# Arduino-Headers.net
KiCad netlist of a schematic drawn in Altium Designer
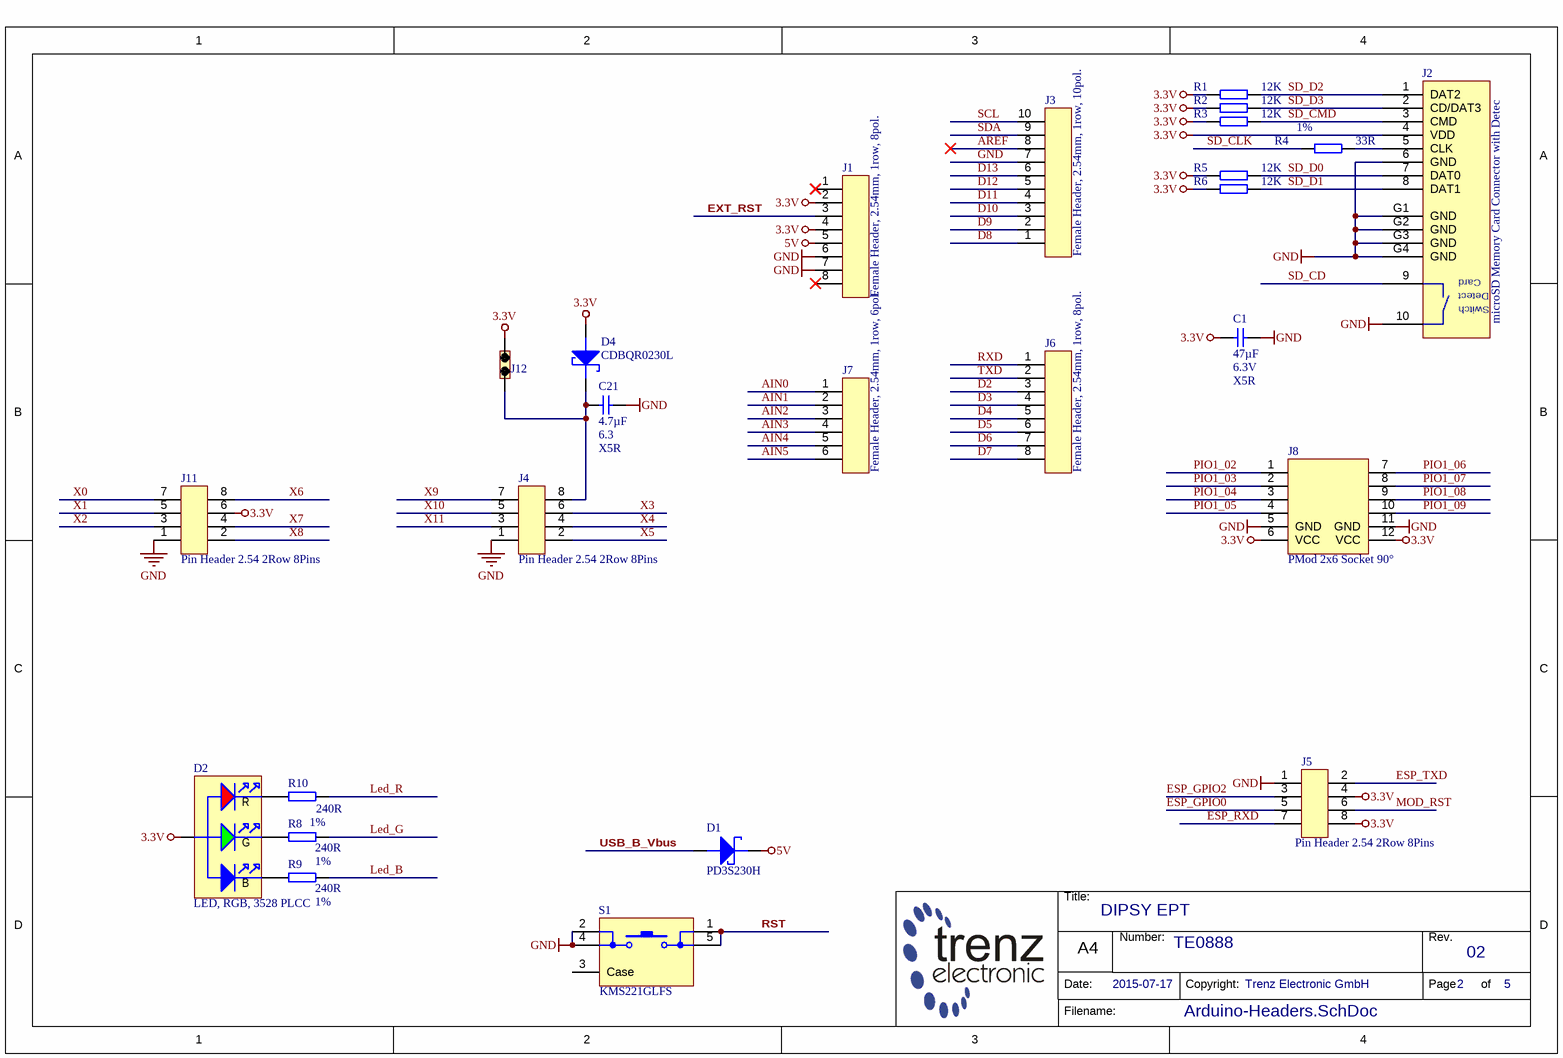
[diagram p0: Arduino-Headers.SchDoc]

(export (version "E")
  (design (tool "Eeschema 10.0.6"))
  (components
    (comp (ref "C1")
      (value "47µF")
      (footprint "CAPC2012X135N")
      (description "KON 47µF 6,3V  X5R SMD 20%")
      (fields
        (field (name "VOLTAGE") "6.3V")
        (field (name "TECHNOLOGY") "X5R")
        (field (name "TOLERANCE") "20%")
      )
      (libsource (lib "TE") (part "CAP-NP"))
    )
    (comp (ref "C21")
      (value "4.7µF")
      (footprint "CAPC1005X60N")
      (description "KON 4.7µF 6.3V X5R SMD 20%")
      (fields
        (field (name "VOLTAGE") "6.3")
        (field (name "TECHNOLOGY") "X5R")
        (field (name "TOLERANCE") "20%")
      )
      (libsource (lib "TE") (part "CAP-NP"))
    )
    (comp (ref "D1") (value "PD3S230H") (footprint "PowerDI323") (libsource (lib "TE") (part "SCHOTTKY")))
    (comp (ref "D2")
      (value "LED, RGB, 3528 PLCC")
      (footprint "PLCC150P360X280X190-4N-WE")
      (libsource (lib "TE") (part "150141M173100"))
    )
    (comp (ref "D4")
      (value "CDBQR0230L")
      (footprint "DIOC1006X55N")
      (fields (field (name "VOLTAGE") "0.2A"))
      (libsource (lib "TE") (part "SCHOTTKY"))
    )
    (comp (ref "J1")
      (value "Female Header, 2.54mm, 1row, 8pol.")
      (footprint "BUCHSENLEISTE-2.54-8-1R")
      (description "Buchsenleiste 1 reihig präz. 8 pol.")
      (libsource (lib "TE") (part "CON-8"))
    )
    (comp (ref "J2")
      (value "microSD Memory Card Connector with Detec")
      (footprint "104031-0811")
      (description "microSD Memory Card Connector with Detect Switch")
      (libsource (lib "TE") (part "104031-0811"))
    )
    (comp (ref "J3")
      (value "Female Header, 2.54mm, 1row, 10pol.")
      (footprint "BUCHSENLEISTE-2.54-10-1R")
      (description "Buchsenleiste 1 reihig präz. 10 pol.")
      (libsource (lib "TE") (part "CON-10"))
    )
    (comp (ref "J4")
      (value "Pin Header 2.54 2Row 8Pins")
      (footprint "STIFTLEISTE2_54 OG 2R-8")
      (description "Stiftleiste gerade 2-reihig, 8pol.")
      (libsource (lib "") (part "CON-8_2"))
    )
    (comp (ref "J5")
      (value "Pin Header 2.54 2Row 8Pins")
      (footprint "STIFTLEISTE2_54 OG 2R-8")
      (description "Stiftleiste gerade 2-reihig, 8pol.")
      (libsource (lib "") (part "CON-8_1"))
    )
    (comp (ref "J6")
      (value "Female Header, 2.54mm, 1row, 8pol.")
      (footprint "BUCHSENLEISTE-2.54-8-1R")
      (description "Buchsenleiste 1 reihig präz. 8 pol.")
      (libsource (lib "TE") (part "CON-8"))
    )
    (comp (ref "J7")
      (value "Female Header, 2.54mm, 1row, 6pol.")
      (footprint "BUCHSENLEISTE-2.54-6-1R")
      (description "Buchsenleiste 1 reihig präz. 6 pol.")
      (libsource (lib "TE") (part "CON-6"))
    )
    (comp (ref "J8")
      (value "PMod 2x6 Socket 90°")
      (footprint "PMod2x6")
      (libsource (lib "TE") (part "PMod2x6"))
    )
    (comp (ref "J11")
      (value "Pin Header 2.54 2Row 8Pins")
      (footprint "STIFTLEISTE2_54 OG 2R-8")
      (description "Stiftleiste gerade 2-reihig, 8pol.")
      (libsource (lib "") (part "CON-8_2"))
    )
    (comp (ref "J12")
      (value "JUMPER2.54-2")
      (footprint "JUMPER2_54-2")
      (description "Stiftleiste gerade 1-reihig, 2pol.")
      (libsource (lib "TE") (part "JUMPER2.54-2"))
    )
    (comp (ref "R1")
      (value "12K")
      (footprint "RESC1005X40N")
      (description "WID SMD 12K 1% 0,063W")
      (libsource (lib "TE") (part "RES"))
    )
    (comp (ref "R2")
      (value "12K")
      (footprint "RESC1005X40N")
      (description "WID SMD 12K 1% 0,063W")
      (libsource (lib "TE") (part "RES"))
    )
    (comp (ref "R3")
      (value "12K")
      (footprint "RESC1005X40N")
      (description "WID SMD 12K 1% 0,063W")
      (libsource (lib "TE") (part "RES"))
    )
    (comp (ref "R4")
      (value "33R")
      (footprint "RESC0603X26N")
      (description "WID SMD 33R 1% 0,05W")
      (fields (field (name "TOLERANCE") "1%"))
      (libsource (lib "TE") (part "RES"))
    )
    (comp (ref "R5")
      (value "12K")
      (footprint "RESC1005X40N")
      (description "WID SMD 12K 1% 0,063W")
      (libsource (lib "TE") (part "RES"))
    )
    (comp (ref "R6")
      (value "12K")
      (footprint "RESC1005X40N")
      (description "WID SMD 12K 1% 0,063W")
      (libsource (lib "TE") (part "RES"))
    )
    (comp (ref "R8")
      (value "240R")
      (footprint "RESC1005X40N")
      (description "WID SMD 240R 1% 0,063W")
      (fields (field (name "TOLERANCE") "1%"))
      (libsource (lib "TE") (part "RES"))
    )
    (comp (ref "R9")
      (value "240R")
      (footprint "RESC1005X40N")
      (description "WID SMD 240R 1% 0,063W")
      (fields (field (name "TOLERANCE") "1%"))
      (libsource (lib "TE") (part "RES"))
    )
    (comp (ref "R10")
      (value "240R")
      (footprint "RESC1005X40N")
      (description "WID SMD 240R 1% 0,063W")
      (fields (field (name "TOLERANCE") "1%"))
      (libsource (lib "TE") (part "RES"))
    )
    (comp (ref "S1")
      (value "KMS221GLFS")
      (footprint "KMS2xxGLFS")
      (description "KMS221GLFS - SWITCH, SPST, 0.05A, 32VDC, SMD")
      (libsource (lib "TE") (part "KMS2xxGLFS"))
    )
  )
  (nets
    (net (code "1") (name "/AIN0") (class "Default") (node (ref "J7") (pin "1") (pintype "passive")))
    (net (code "2") (name "/AIN1") (class "Default") (node (ref "J7") (pin "2") (pintype "passive")))
    (net (code "3") (name "/AIN2") (class "Default") (node (ref "J7") (pin "3") (pintype "passive")))
    (net (code "4") (name "/AIN3") (class "Default") (node (ref "J7") (pin "4") (pintype "passive")))
    (net (code "5") (name "/AIN4") (class "Default") (node (ref "J7") (pin "5") (pintype "passive")))
    (net (code "6") (name "/AIN5") (class "Default") (node (ref "J7") (pin "6") (pintype "passive")))
    (net (code "7") (name "/AREF") (class "Default")
      (node (ref "J3") (pin "8") (pinfunction "8_8") (pintype "passive+no_connect"))
    )
    (net (code "8") (name "/D2") (class "Default") (node (ref "J6") (pin "3") (pintype "passive")))
    (net (code "9") (name "/D3") (class "Default") (node (ref "J6") (pin "4") (pintype "passive")))
    (net (code "10") (name "/D4") (class "Default") (node (ref "J6") (pin "5") (pintype "passive")))
    (net (code "11") (name "/D5") (class "Default") (node (ref "J6") (pin "6") (pintype "passive")))
    (net (code "12") (name "/D6") (class "Default") (node (ref "J6") (pin "7") (pintype "passive")))
    (net (code "13") (name "/D7") (class "Default") (node (ref "J6") (pin "8") (pintype "passive")))
    (net (code "14") (name "/D8") (class "Default")
      (node (ref "J3") (pin "1") (pinfunction "1_1") (pintype "passive"))
    )
    (net (code "15") (name "/D9") (class "Default")
      (node (ref "J3") (pin "2") (pinfunction "2_2") (pintype "passive"))
    )
    (net (code "16") (name "/D10") (class "Default")
      (node (ref "J3") (pin "3") (pinfunction "3_3") (pintype "passive"))
    )
    (net (code "17") (name "/D11") (class "Default")
      (node (ref "J3") (pin "4") (pinfunction "4_4") (pintype "passive"))
    )
    (net (code "18") (name "/D12") (class "Default")
      (node (ref "J3") (pin "5") (pinfunction "5_5") (pintype "passive"))
    )
    (net (code "19") (name "/D13") (class "Default")
      (node (ref "J3") (pin "6") (pinfunction "6_6") (pintype "passive"))
    )
    (net (code "20") (name "/ESP_GPIO0") (class "Default") (node (ref "J5") (pin "5") (pintype "passive")))
    (net (code "21") (name "/ESP_GPIO2") (class "Default") (node (ref "J5") (pin "3") (pintype "passive")))
    (net (code "22") (name "/ESP_RXD") (class "Default") (node (ref "J5") (pin "7") (pintype "passive")))
    (net (code "23") (name "/ESP_TXD") (class "Default") (node (ref "J5") (pin "2") (pintype "passive")))
    (net (code "24") (name "/EXT_RST") (class "Default") (node (ref "J1") (pin "3") (pintype "passive")))
    (net (code "25") (name "/Led_B") (class "Default")
      (node (ref "R9") (pin "1") (pinfunction "1_1") (pintype "passive"))
    )
    (net (code "26") (name "/Led_G") (class "Default")
      (node (ref "R8") (pin "1") (pinfunction "1_1") (pintype "passive"))
    )
    (net (code "27") (name "/Led_R") (class "Default")
      (node (ref "R10") (pin "1") (pinfunction "1_1") (pintype "passive"))
    )
    (net (code "28") (name "/MOD_RST") (class "Default") (node (ref "J5") (pin "6") (pintype "passive")))
    (net (code "29") (name "/PIO1_02") (class "Default") (node (ref "J8") (pin "1") (pintype "passive")))
    (net (code "30") (name "/PIO1_03") (class "Default") (node (ref "J8") (pin "2") (pintype "passive")))
    (net (code "31") (name "/PIO1_04") (class "Default") (node (ref "J8") (pin "3") (pintype "passive")))
    (net (code "32") (name "/PIO1_05") (class "Default") (node (ref "J8") (pin "4") (pintype "passive")))
    (net (code "33") (name "/PIO1_06") (class "Default") (node (ref "J8") (pin "7") (pintype "passive")))
    (net (code "34") (name "/PIO1_07") (class "Default") (node (ref "J8") (pin "8") (pintype "passive")))
    (net (code "35") (name "/PIO1_08") (class "Default") (node (ref "J8") (pin "9") (pintype "passive")))
    (net (code "36") (name "/PIO1_09") (class "Default") (node (ref "J8") (pin "10") (pintype "passive")))
    (net (code "37") (name "/RST") (class "Default")
      (node (ref "S1") (pin "1") (pinfunction "1_1") (pintype "passive"))
      (node (ref "S1") (pin "5") (pinfunction "5_5") (pintype "passive"))
    )
    (net (code "38") (name "/RXD") (class "Default") (node (ref "J6") (pin "1") (pintype "passive")))
    (net (code "39") (name "/SCL") (class "Default")
      (node (ref "J3") (pin "10") (pinfunction "10_10") (pintype "passive"))
    )
    (net (code "40") (name "/SDA") (class "Default")
      (node (ref "J3") (pin "9") (pinfunction "9_9") (pintype "passive"))
    )
    (net (code "41") (name "/SD_CD") (class "Default")
      (node (ref "J2") (pin "9") (pinfunction "CDSW_9") (pintype "passive"))
    )
    (net (code "42") (name "/SD_CLK") (class "Default")
      (node (ref "R4") (pin "1") (pinfunction "1_1") (pintype "passive"))
    )
    (net (code "43") (name "/SD_CMD") (class "Default")
      (node (ref "J2") (pin "3") (pinfunction "CMD_3") (pintype "passive"))
      (node (ref "R3") (pin "2") (pinfunction "2_2") (pintype "passive"))
    )
    (net (code "44") (name "/SD_D0") (class "Default")
      (node (ref "J2") (pin "7") (pinfunction "DAT0_7") (pintype "passive"))
      (node (ref "R5") (pin "2") (pinfunction "2_2") (pintype "passive"))
    )
    (net (code "45") (name "/SD_D1") (class "Default")
      (node (ref "J2") (pin "8") (pinfunction "DAT1_8") (pintype "passive"))
      (node (ref "R6") (pin "2") (pinfunction "2_2") (pintype "passive"))
    )
    (net (code "46") (name "/SD_D2") (class "Default")
      (node (ref "J2") (pin "1") (pinfunction "DAT2_1") (pintype "passive"))
      (node (ref "R1") (pin "2") (pinfunction "2_2") (pintype "passive"))
    )
    (net (code "47") (name "/SD_D3") (class "Default")
      (node (ref "J2") (pin "2") (pinfunction "CD/DAT3_2") (pintype "passive"))
      (node (ref "R2") (pin "2") (pinfunction "2_2") (pintype "passive"))
    )
    (net (code "48") (name "/TXD") (class "Default") (node (ref "J6") (pin "2") (pintype "passive")))
    (net (code "49") (name "/USB_B_Vbus") (class "Default")
      (node (ref "D1") (pin "2") (pinfunction "ANODE_2") (pintype "passive"))
    )
    (net (code "50") (name "/X0") (class "Default") (node (ref "J11") (pin "7") (pintype "passive")))
    (net (code "51") (name "/X1") (class "Default") (node (ref "J11") (pin "5") (pintype "passive")))
    (net (code "52") (name "/X2") (class "Default") (node (ref "J11") (pin "3") (pintype "passive")))
    (net (code "53") (name "/X3") (class "Default") (node (ref "J4") (pin "6") (pintype "passive")))
    (net (code "54") (name "/X4") (class "Default") (node (ref "J4") (pin "4") (pintype "passive")))
    (net (code "55") (name "/X5") (class "Default") (node (ref "J4") (pin "2") (pintype "passive")))
    (net (code "56") (name "/X6") (class "Default") (node (ref "J11") (pin "8") (pintype "passive")))
    (net (code "57") (name "/X7") (class "Default") (node (ref "J11") (pin "4") (pintype "passive")))
    (net (code "58") (name "/X8") (class "Default") (node (ref "J11") (pin "2") (pintype "passive")))
    (net (code "59") (name "/X9") (class "Default") (node (ref "J4") (pin "7") (pintype "passive")))
    (net (code "60") (name "/X10") (class "Default") (node (ref "J4") (pin "5") (pintype "passive")))
    (net (code "61") (name "/X11") (class "Default") (node (ref "J4") (pin "3") (pintype "passive")))
    (net (code "62") (name "3.3V") (class "Default")
      (node (ref "C1") (pin "1") (pinfunction "1_1") (pintype "passive"))
      (node (ref "D2") (pin "1") (pinfunction "ANODE_1") (pintype "passive"))
      (node (ref "D4") (pin "2") (pinfunction "ANODE_2") (pintype "passive"))
      (node (ref "J1") (pin "2") (pintype "passive"))
      (node (ref "J1") (pin "4") (pintype "passive"))
      (node (ref "J11") (pin "6") (pintype "passive"))
      (node (ref "J12") (pin "1") (pinfunction "1_1") (pintype "passive"))
      (node (ref "J2") (pin "4") (pinfunction "VDD_4") (pintype "passive"))
      (node (ref "J5") (pin "4") (pintype "passive"))
      (node (ref "J5") (pin "8") (pintype "passive"))
      (node (ref "J8") (pin "12") (pinfunction "VCC_12") (pintype "power_in"))
      (node (ref "J8") (pin "6") (pinfunction "VCC_6") (pintype "power_in"))
      (node (ref "R1") (pin "1") (pinfunction "1_1") (pintype "passive"))
      (node (ref "R2") (pin "1") (pinfunction "1_1") (pintype "passive"))
      (node (ref "R3") (pin "1") (pinfunction "1_1") (pintype "passive"))
      (node (ref "R5") (pin "1") (pinfunction "1_1") (pintype "passive"))
      (node (ref "R6") (pin "1") (pinfunction "1_1") (pintype "passive"))
    )
    (net (code "63") (name "5V") (class "Default")
      (node (ref "D1") (pin "1") (pinfunction "KATHODE_1") (pintype "passive"))
      (node (ref "J1") (pin "5") (pintype "passive"))
    )
    (net (code "64") (name "GND") (class "Default")
      (node (ref "C1") (pin "2") (pinfunction "2_2") (pintype "passive"))
      (node (ref "C21") (pin "1") (pinfunction "1_1") (pintype "passive"))
      (node (ref "J1") (pin "6") (pintype "passive"))
      (node (ref "J1") (pin "7") (pintype "passive"))
      (node (ref "J11") (pin "1") (pintype "passive"))
      (node (ref "J2") (pin "10") (pinfunction "CDSW_10") (pintype "passive"))
      (node (ref "J2") (pin "6") (pinfunction "GND_6") (pintype "passive"))
      (node (ref "J2") (pin "G1") (pinfunction "GND_G1") (pintype "passive"))
      (node (ref "J2") (pin "G2") (pinfunction "GND_G2") (pintype "passive"))
      (node (ref "J2") (pin "G3") (pinfunction "GND_G3") (pintype "passive"))
      (node (ref "J2") (pin "G4") (pinfunction "GND_G4") (pintype "passive"))
      (node (ref "J3") (pin "7") (pinfunction "7_7") (pintype "passive"))
      (node (ref "J4") (pin "1") (pintype "passive"))
      (node (ref "J5") (pin "1") (pintype "passive"))
      (node (ref "J8") (pin "11") (pinfunction "GND_11") (pintype "power_in"))
      (node (ref "J8") (pin "5") (pinfunction "GND_5") (pintype "power_in"))
      (node (ref "S1") (pin "2") (pinfunction "2_2") (pintype "passive"))
      (node (ref "S1") (pin "4") (pinfunction "4_4") (pintype "passive"))
    )
    (net (code "65") (name "Net-(D2-BLUE)") (class "Default")
      (node (ref "D2") (pin "2") (pinfunction "BLUE_2") (pintype "passive"))
      (node (ref "R9") (pin "2") (pinfunction "2_2") (pintype "passive"))
    )
    (net (code "66") (name "Net-(D2-GREEN)") (class "Default")
      (node (ref "D2") (pin "4") (pinfunction "GREEN_4") (pintype "passive"))
      (node (ref "R8") (pin "2") (pinfunction "2_2") (pintype "passive"))
    )
    (net (code "67") (name "Net-(D2-RED)") (class "Default")
      (node (ref "D2") (pin "3") (pinfunction "RED_3") (pintype "passive"))
      (node (ref "R10") (pin "2") (pinfunction "2_2") (pintype "passive"))
    )
    (net (code "68") (name "Net-(D4-KATHODE)") (class "Default")
      (node (ref "C21") (pin "2") (pinfunction "2_2") (pintype "passive"))
      (node (ref "D4") (pin "1") (pinfunction "KATHODE_1") (pintype "passive"))
      (node (ref "J12") (pin "2") (pinfunction "2_2") (pintype "passive"))
      (node (ref "J4") (pin "8") (pintype "passive"))
    )
    (net (code "69") (name "Net-(J2-CLK)") (class "Default")
      (node (ref "J2") (pin "5") (pinfunction "CLK_5") (pintype "passive"))
      (node (ref "R4") (pin "2") (pinfunction "2_2") (pintype "passive"))
    )
    (net (code "70") (name "unconnected-(J1-Pad1)") (class "Default")
      (node (ref "J1") (pin "1") (pintype "passive+no_connect"))
    )
    (net (code "71") (name "unconnected-(J1-Pad8)") (class "Default")
      (node (ref "J1") (pin "8") (pintype "passive+no_connect"))
    )
    (net (code "72") (name "unconnected-(S1-Case-Pad3)") (class "Default")
      (node (ref "S1") (pin "3") (pinfunction "Case_3") (pintype "passive"))
    )
  )
)
